# converter.net
KiCad netlist of a schematic drawn in EAGLE
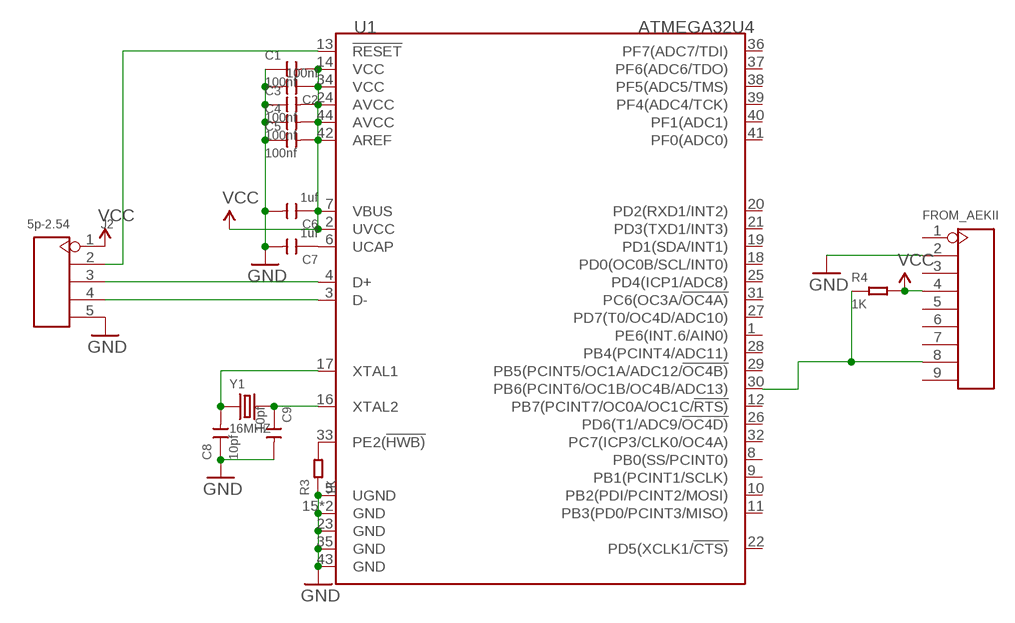
[diagram p0: schematic, sheet 1]
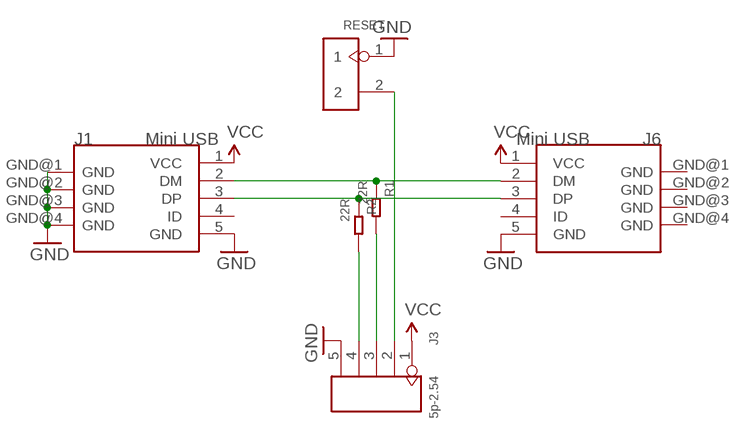
[diagram p1: schematic, sheet 2]

(export (version "E")
  (design (tool "Eeschema 10.0.6"))
  (components
    (comp (ref "J1")
      (value "Mini USB")
      (footprint "eagle-import:MINIUSB5+4P-0.8-90D")
      (fields (field (name "MPN") "ST-USB-013A"))
      (libsource (lib "eagle-import") (part "MINI-USB2.0-RECEPT-5POS-4-LEGS-(ST-USB-013A)"))
    )
    (comp (ref "J3")
      (value "5p-2.54")
      (footprint "eagle-import:H5-2.54")
      (fields (field (name "MPN") "F185-1105A0BSYA1"))
      (libsource (lib "eagle-import") (part "DIP-BLACK-FEMALE-HEADER-VERT(5P-2.54)"))
    )
    (comp (ref "J6")
      (value "Mini USB")
      (footprint "eagle-import:MINIUSB5+4P-0.8-90D")
      (fields (field (name "MPN") "ST-USB-013A"))
      (libsource (lib "eagle-import") (part "MINI-USB2.0-RECEPT-5POS-4-LEGS-(ST-USB-013A)"))
    )
    (comp (ref "R1")
      (value "22R")
      (footprint "eagle-import:R0603")
      (fields (field (name "MPN") "RC0603JR-0722RL"))
      (libsource (lib "eagle-import") (part "SMD-RES-22R-5%-1/10W(0603)"))
    )
    (comp (ref "R2")
      (value "22R")
      (footprint "eagle-import:R0603")
      (fields (field (name "MPN") "RC0603JR-0722RL"))
      (libsource (lib "eagle-import") (part "SMD-RES-22R-5%-1/10W(0603)"))
    )
    (comp (ref "RESET")
      (value "DIP-BLACK-FEMALE-HEADER-VERT(2P-2.54)")
      (footprint "eagle-import:H2-2.54")
      (fields (field (name "MPN") "F185-1102A1BSYA1"))
      (libsource (lib "eagle-import") (part "DIP-BLACK-FEMALE-HEADER-VERT(2P-2.54)"))
    )
    (comp (ref "C1")
      (value "100nf")
      (footprint "eagle-import:C0603")
      (fields (field (name "MPN") "CC0603KRX7R9BB104"))
      (libsource (lib "eagle-import") (part "CERAMIC-100NF-50V-10%-X7R(0603)"))
    )
    (comp (ref "C2")
      (value "100nf")
      (footprint "eagle-import:C0603")
      (fields (field (name "MPN") "CC0603KRX7R9BB104"))
      (libsource (lib "eagle-import") (part "CERAMIC-100NF-50V-10%-X7R(0603)"))
    )
    (comp (ref "C3")
      (value "100nf")
      (footprint "eagle-import:C0603")
      (fields (field (name "MPN") "CC0603KRX7R9BB104"))
      (libsource (lib "eagle-import") (part "CERAMIC-100NF-50V-10%-X7R(0603)"))
    )
    (comp (ref "C4")
      (value "100nf")
      (footprint "eagle-import:C0603")
      (fields (field (name "MPN") "CC0603KRX7R9BB104"))
      (libsource (lib "eagle-import") (part "CERAMIC-100NF-50V-10%-X7R(0603)"))
    )
    (comp (ref "C5")
      (value "100nf")
      (footprint "eagle-import:C0603")
      (fields (field (name "MPN") "CC0603KRX7R9BB104"))
      (libsource (lib "eagle-import") (part "CERAMIC-100NF-50V-10%-X7R(0603)"))
    )
    (comp (ref "C6")
      (value "1uf")
      (footprint "eagle-import:C0603")
      (fields (field (name "MPN") "CC0603KRX7R8BB105"))
      (libsource (lib "eagle-import") (part "CERAMIC-1UF-25V-10%-X7R(0603)"))
    )
    (comp (ref "C7")
      (value "1uf")
      (footprint "eagle-import:C0603")
      (fields (field (name "MPN") "CC0603KRX7R8BB105"))
      (libsource (lib "eagle-import") (part "CERAMIC-1UF-25V-10%-X7R(0603)"))
    )
    (comp (ref "C8")
      (value "10pf")
      (footprint "eagle-import:C0603")
      (libsource (lib "eagle-import") (part "CERAMIC-10PF-50V-5%-NPO(0603)"))
    )
    (comp (ref "C9")
      (value "10pf")
      (footprint "eagle-import:C0603")
      (libsource (lib "eagle-import") (part "CERAMIC-10PF-50V-5%-NPO(0603)"))
    )
    (comp (ref "FROM_AEKII")
      (value "DIP-BLACK-FEMALE-HEADER-VERT(9P-2.0)")
      (footprint "eagle-import:H9-2.0")
      (libsource (lib "eagle-import") (part "DIP-BLACK-FEMALE-HEADER-VERT(9P-2.0)"))
    )
    (comp (ref "J2")
      (value "5p-2.54")
      (footprint "eagle-import:H5-2.54")
      (fields (field (name "MPN") "F185-1105A0BSYA1"))
      (libsource (lib "eagle-import") (part "DIP-BLACK-FEMALE-HEADER-VERT(5P-2.54)"))
    )
    (comp (ref "R3")
      (value "1K")
      (footprint "eagle-import:R0603")
      (fields (field (name "MPN") "RC0603FR-071KL"))
      (libsource (lib "eagle-import") (part "SMD-RES-1K-1%-1/10W(0603)"))
    )
    (comp (ref "R4")
      (value "1K")
      (footprint "eagle-import:R0603")
      (fields (field (name "MPN") "RC0603FR-071KL"))
      (libsource (lib "eagle-import") (part "SMD-RES-1K-1%-1/10W(0603)"))
    )
    (comp (ref "U1")
      (value "ATMEGA32U4")
      (footprint "eagle-import:QFN44G-0.5-7X7MM")
      (fields (field (name "MPN") "ATMEGA32U4-MUR"))
      (libsource (lib "eagle-import") (part "MCU-ATMEGA32U4-MUR(VQFN44)"))
    )
    (comp (ref "Y1")
      (value "16MHZ")
      (footprint "eagle-import:X2-SMD-5.0X3.2X1.3MM")
      (fields (field (name "MPN") "X053201602002"))
      (libsource (lib "eagle-import") (part "SMD-CRYSTAL-16MHZ-8PF-20PPM-40R(2P-5.0X3.2MM)"))
    )
  )
  (nets
    (net (code "1") (name "GND") (class "Default")
      (node (ref "C1") (pin "1") (pinfunction "1_1") (pintype "passive"))
      (node (ref "C2") (pin "2") (pinfunction "2_2") (pintype "passive"))
      (node (ref "C3") (pin "1") (pinfunction "1_1") (pintype "passive"))
      (node (ref "C4") (pin "1") (pinfunction "1_1") (pintype "passive"))
      (node (ref "C5") (pin "1") (pinfunction "1_1") (pintype "passive"))
      (node (ref "C6") (pin "2") (pinfunction "2_2") (pintype "passive"))
      (node (ref "C7") (pin "2") (pinfunction "2_2") (pintype "passive"))
      (node (ref "C8") (pin "1") (pinfunction "1_1") (pintype "passive"))
      (node (ref "C9") (pin "2") (pinfunction "2_2") (pintype "passive"))
      (node (ref "FROM_AEKII") (pin "2") (pinfunction "2_2") (pintype "bidirectional"))
      (node (ref "J1") (pin "5") (pinfunction "GND_5") (pintype "bidirectional"))
      (node (ref "J1") (pin "GND@1") (pinfunction "GND_GND@1") (pintype "bidirectional"))
      (node (ref "J1") (pin "GND@2") (pinfunction "GND_GND@2") (pintype "bidirectional"))
      (node (ref "J1") (pin "GND@3") (pinfunction "GND_GND@3") (pintype "bidirectional"))
      (node (ref "J1") (pin "GND@4") (pinfunction "GND_GND@4") (pintype "bidirectional"))
      (node (ref "J2") (pin "5") (pinfunction "5_5") (pintype "bidirectional"))
      (node (ref "J3") (pin "5") (pinfunction "5_5") (pintype "bidirectional"))
      (node (ref "J6") (pin "5") (pinfunction "GND_5") (pintype "bidirectional"))
      (node (ref "R3") (pin "1") (pinfunction "1_1") (pintype "passive"))
      (node (ref "RESET") (pin "1") (pinfunction "1_1") (pintype "bidirectional"))
      (node (ref "U1") (pin "15") (pinfunction "GND_15") (pintype "bidirectional"))
      (node (ref "U1") (pin "23") (pinfunction "GND_23") (pintype "bidirectional"))
      (node (ref "U1") (pin "35") (pinfunction "GND_35") (pintype "bidirectional"))
      (node (ref "U1") (pin "43") (pinfunction "GND_43") (pintype "bidirectional"))
      (node (ref "U1") (pin "5") (pinfunction "UGND_5") (pintype "bidirectional"))
      (node (ref "U1") (pin "TAB") (pinfunction "GND_TAB") (pintype "bidirectional"))
    )
    (net (code "2") (name "Net-(J1-DM)") (class "Default")
      (node (ref "J1") (pin "2") (pinfunction "DM_2") (pintype "bidirectional"))
      (node (ref "J6") (pin "2") (pinfunction "DM_2") (pintype "bidirectional"))
      (node (ref "R1") (pin "1") (pinfunction "1_1") (pintype "passive"))
    )
    (net (code "3") (name "Net-(J1-DP)") (class "Default")
      (node (ref "J1") (pin "3") (pinfunction "DP_3") (pintype "bidirectional"))
      (node (ref "J6") (pin "3") (pinfunction "DP_3") (pintype "bidirectional"))
      (node (ref "R2") (pin "1") (pinfunction "1_1") (pintype "passive"))
    )
    (net (code "4") (name "Net-(J3-Pad2)") (class "Default")
      (node (ref "J3") (pin "2") (pinfunction "2_2") (pintype "bidirectional"))
      (node (ref "RESET") (pin "2") (pinfunction "2_2") (pintype "bidirectional"))
    )
    (net (code "5") (name "Net-(J3-Pad3)") (class "Default")
      (node (ref "J3") (pin "3") (pinfunction "3_3") (pintype "bidirectional"))
      (node (ref "R1") (pin "2") (pinfunction "2_2") (pintype "passive"))
    )
    (net (code "6") (name "Net-(J3-Pad4)") (class "Default")
      (node (ref "J3") (pin "4") (pinfunction "4_4") (pintype "bidirectional"))
      (node (ref "R2") (pin "2") (pinfunction "2_2") (pintype "passive"))
    )
    (net (code "7") (name "Net-(U1-D+)") (class "Default")
      (node (ref "J2") (pin "3") (pinfunction "3_3") (pintype "bidirectional"))
      (node (ref "U1") (pin "4") (pinfunction "D+_4") (pintype "bidirectional"))
    )
    (net (code "8") (name "Net-(U1-D-)") (class "Default")
      (node (ref "J2") (pin "4") (pinfunction "4_4") (pintype "bidirectional"))
      (node (ref "U1") (pin "3") (pinfunction "D-_3") (pintype "bidirectional"))
    )
    (net (code "9") (name "Net-(U1-PB6(PCINT6{slash}OC1B{slash}OC4B{slash}ADC13))") (class "Default")
      (node (ref "FROM_AEKII") (pin "8") (pinfunction "8_8") (pintype "bidirectional"))
      (node (ref "R4") (pin "1") (pinfunction "1_1") (pintype "passive"))
      (node (ref "U1") (pin "30") (pinfunction "PB6(PCINT6/OC1B/OC4B/ADC13)_30") (pintype "bidirectional"))
    )
    (net (code "10") (name "Net-(U1-PE2(~{HWB}))") (class "Default")
      (node (ref "R3") (pin "2") (pinfunction "2_2") (pintype "passive"))
      (node (ref "U1") (pin "33") (pinfunction "PE2(~{HWB})_33") (pintype "bidirectional"))
    )
    (net (code "11") (name "Net-(U1-UCAP)") (class "Default")
      (node (ref "C7") (pin "1") (pinfunction "1_1") (pintype "passive"))
      (node (ref "U1") (pin "6") (pinfunction "UCAP_6") (pintype "bidirectional"))
    )
    (net (code "12") (name "Net-(U1-XTAL1)") (class "Default")
      (node (ref "C8") (pin "2") (pinfunction "2_2") (pintype "passive"))
      (node (ref "U1") (pin "17") (pinfunction "XTAL1_17") (pintype "bidirectional"))
      (node (ref "Y1") (pin "1") (pinfunction "1_1") (pintype "passive"))
    )
    (net (code "13") (name "Net-(U1-XTAL2)") (class "Default")
      (node (ref "C9") (pin "1") (pinfunction "1_1") (pintype "passive"))
      (node (ref "U1") (pin "16") (pinfunction "XTAL2_16") (pintype "bidirectional"))
      (node (ref "Y1") (pin "2") (pinfunction "2_2") (pintype "passive"))
    )
    (net (code "14") (name "Net-(U1-~{RESET})") (class "Default")
      (node (ref "J2") (pin "2") (pinfunction "2_2") (pintype "bidirectional"))
      (node (ref "U1") (pin "13") (pinfunction "~{RESET}_13") (pintype "bidirectional"))
    )
    (net (code "15") (name "VCC") (class "Default")
      (node (ref "C1") (pin "2") (pinfunction "2_2") (pintype "passive"))
      (node (ref "C2") (pin "1") (pinfunction "1_1") (pintype "passive"))
      (node (ref "C3") (pin "2") (pinfunction "2_2") (pintype "passive"))
      (node (ref "C4") (pin "2") (pinfunction "2_2") (pintype "passive"))
      (node (ref "C5") (pin "2") (pinfunction "2_2") (pintype "passive"))
      (node (ref "C6") (pin "1") (pinfunction "1_1") (pintype "passive"))
      (node (ref "FROM_AEKII") (pin "4") (pinfunction "4_4") (pintype "bidirectional"))
      (node (ref "J1") (pin "1") (pinfunction "VCC_1") (pintype "bidirectional"))
      (node (ref "J2") (pin "1") (pinfunction "1_1") (pintype "bidirectional"))
      (node (ref "J3") (pin "1") (pinfunction "1_1") (pintype "bidirectional"))
      (node (ref "J6") (pin "1") (pinfunction "VCC_1") (pintype "bidirectional"))
      (node (ref "R4") (pin "2") (pinfunction "2_2") (pintype "passive"))
      (node (ref "U1") (pin "14") (pinfunction "VCC_14") (pintype "bidirectional"))
      (node (ref "U1") (pin "2") (pinfunction "UVCC_2") (pintype "bidirectional"))
      (node (ref "U1") (pin "24") (pinfunction "AVCC_24") (pintype "bidirectional"))
      (node (ref "U1") (pin "34") (pinfunction "VCC_34") (pintype "bidirectional"))
      (node (ref "U1") (pin "42") (pinfunction "AREF_42") (pintype "bidirectional"))
      (node (ref "U1") (pin "44") (pinfunction "AVCC_44") (pintype "bidirectional"))
      (node (ref "U1") (pin "7") (pinfunction "VBUS_7") (pintype "bidirectional"))
    )
    (net (code "16") (name "unconnected-(FROM_AEKII-Pad1)") (class "Default")
      (node (ref "FROM_AEKII") (pin "1") (pinfunction "1_1") (pintype "bidirectional"))
    )
    (net (code "17") (name "unconnected-(FROM_AEKII-Pad3)") (class "Default")
      (node (ref "FROM_AEKII") (pin "3") (pinfunction "3_3") (pintype "bidirectional"))
    )
    (net (code "18") (name "unconnected-(FROM_AEKII-Pad5)") (class "Default")
      (node (ref "FROM_AEKII") (pin "5") (pinfunction "5_5") (pintype "bidirectional"))
    )
    (net (code "19") (name "unconnected-(FROM_AEKII-Pad6)") (class "Default")
      (node (ref "FROM_AEKII") (pin "6") (pinfunction "6_6") (pintype "bidirectional"))
    )
    (net (code "20") (name "unconnected-(FROM_AEKII-Pad7)") (class "Default")
      (node (ref "FROM_AEKII") (pin "7") (pinfunction "7_7") (pintype "bidirectional"))
    )
    (net (code "21") (name "unconnected-(FROM_AEKII-Pad9)") (class "Default")
      (node (ref "FROM_AEKII") (pin "9") (pinfunction "9_9") (pintype "bidirectional"))
    )
    (net (code "22") (name "unconnected-(J1-ID-Pad4)") (class "Default")
      (node (ref "J1") (pin "4") (pinfunction "ID_4") (pintype "bidirectional"))
    )
    (net (code "23") (name "unconnected-(J6-GND-PadGND@1)") (class "Default")
      (node (ref "J6") (pin "GND@1") (pinfunction "GND_GND@1") (pintype "bidirectional"))
    )
    (net (code "24") (name "unconnected-(J6-GND-PadGND@2)") (class "Default")
      (node (ref "J6") (pin "GND@2") (pinfunction "GND_GND@2") (pintype "bidirectional"))
    )
    (net (code "25") (name "unconnected-(J6-GND-PadGND@3)") (class "Default")
      (node (ref "J6") (pin "GND@3") (pinfunction "GND_GND@3") (pintype "bidirectional"))
    )
    (net (code "26") (name "unconnected-(J6-GND-PadGND@4)") (class "Default")
      (node (ref "J6") (pin "GND@4") (pinfunction "GND_GND@4") (pintype "bidirectional"))
    )
    (net (code "27") (name "unconnected-(J6-ID-Pad4)") (class "Default")
      (node (ref "J6") (pin "4") (pinfunction "ID_4") (pintype "bidirectional"))
    )
    (net (code "28") (name "unconnected-(U1-PB0(SS{slash}PCINT0)-Pad8)") (class "Default")
      (node (ref "U1") (pin "8") (pinfunction "PB0(SS/PCINT0)_8") (pintype "bidirectional"))
    )
    (net (code "29") (name "unconnected-(U1-PB1(PCINT1{slash}SCLK)-Pad9)") (class "Default")
      (node (ref "U1") (pin "9") (pinfunction "PB1(PCINT1/SCLK)_9") (pintype "bidirectional"))
    )
    (net (code "30") (name "unconnected-(U1-PB2(PDI{slash}PCINT2{slash}MOSI)-Pad10)") (class "Default")
      (node (ref "U1") (pin "10") (pinfunction "PB2(PDI/PCINT2/MOSI)_10") (pintype "bidirectional"))
    )
    (net (code "31") (name "unconnected-(U1-PB3(PD0{slash}PCINT3{slash}MISO)-Pad11)") (class "Default")
      (node (ref "U1") (pin "11") (pinfunction "PB3(PD0/PCINT3/MISO)_11") (pintype "bidirectional"))
    )
    (net (code "32") (name "unconnected-(U1-PB4(PCINT4{slash}ADC11)-Pad28)") (class "Default")
      (node (ref "U1") (pin "28") (pinfunction "PB4(PCINT4/ADC11)_28") (pintype "bidirectional"))
    )
    (net (code "33") (name "unconnected-(U1-PB5(PCINT5{slash}OC1A{slash}ADC12{slash}~{OC4B})-Pad29)") (class "Default")
      (node (ref "U1") (pin "29") (pinfunction "PB5(PCINT5/OC1A/ADC12/~{OC4B})_29") (pintype "bidirectional"))
    )
    (net (code "34") (name "unconnected-(U1-PB7(PCINT7{slash}OC0A{slash}OC1C{slash}~{RTS})-Pad12)") (class "Default")
      (node (ref "U1") (pin "12") (pinfunction "PB7(PCINT7/OC0A/OC1C/~{RTS})_12") (pintype "bidirectional"))
    )
    (net (code "35") (name "unconnected-(U1-PC6(OC3A{slash}~{OC4A})-Pad31)") (class "Default")
      (node (ref "U1") (pin "31") (pinfunction "PC6(OC3A/~{OC4A})_31") (pintype "bidirectional"))
    )
    (net (code "36") (name "unconnected-(U1-PC7(ICP3{slash}CLK0{slash}OC4A)-Pad32)") (class "Default")
      (node (ref "U1") (pin "32") (pinfunction "PC7(ICP3/CLK0/OC4A)_32") (pintype "bidirectional"))
    )
    (net (code "37") (name "unconnected-(U1-PD0(OC0B{slash}SCL{slash}INT0)-Pad18)") (class "Default")
      (node (ref "U1") (pin "18") (pinfunction "PD0(OC0B/SCL/INT0)_18") (pintype "bidirectional"))
    )
    (net (code "38") (name "unconnected-(U1-PD1(SDA{slash}INT1)-Pad19)") (class "Default")
      (node (ref "U1") (pin "19") (pinfunction "PD1(SDA/INT1)_19") (pintype "bidirectional"))
    )
    (net (code "39") (name "unconnected-(U1-PD2(RXD1{slash}INT2)-Pad20)") (class "Default")
      (node (ref "U1") (pin "20") (pinfunction "PD2(RXD1/INT2)_20") (pintype "bidirectional"))
    )
    (net (code "40") (name "unconnected-(U1-PD3(TXD1{slash}INT3)-Pad21)") (class "Default")
      (node (ref "U1") (pin "21") (pinfunction "PD3(TXD1/INT3)_21") (pintype "bidirectional"))
    )
    (net (code "41") (name "unconnected-(U1-PD4(ICP1{slash}ADC8)-Pad25)") (class "Default")
      (node (ref "U1") (pin "25") (pinfunction "PD4(ICP1/ADC8)_25") (pintype "bidirectional"))
    )
    (net (code "42") (name "unconnected-(U1-PD5(XCLK1{slash}~{CTS})-Pad22)") (class "Default")
      (node (ref "U1") (pin "22") (pinfunction "PD5(XCLK1/~{CTS})_22") (pintype "bidirectional"))
    )
    (net (code "43") (name "unconnected-(U1-PD6(T1{slash}ADC9{slash}~{OC4D})-Pad26)") (class "Default")
      (node (ref "U1") (pin "26") (pinfunction "PD6(T1/ADC9/~{OC4D})_26") (pintype "bidirectional"))
    )
    (net (code "44") (name "unconnected-(U1-PD7(T0{slash}OC4D{slash}ADC10)-Pad27)") (class "Default")
      (node (ref "U1") (pin "27") (pinfunction "PD7(T0/OC4D/ADC10)_27") (pintype "bidirectional"))
    )
    (net (code "45") (name "unconnected-(U1-PE6(INT.6{slash}AIN0)-Pad1)") (class "Default")
      (node (ref "U1") (pin "1") (pinfunction "PE6(INT.6/AIN0)_1") (pintype "bidirectional"))
    )
    (net (code "46") (name "unconnected-(U1-PF0(ADC0)-Pad41)") (class "Default")
      (node (ref "U1") (pin "41") (pinfunction "PF0(ADC0)_41") (pintype "bidirectional"))
    )
    (net (code "47") (name "unconnected-(U1-PF1(ADC1)-Pad40)") (class "Default")
      (node (ref "U1") (pin "40") (pinfunction "PF1(ADC1)_40") (pintype "bidirectional"))
    )
    (net (code "48") (name "unconnected-(U1-PF4(ADC4{slash}TCK)-Pad39)") (class "Default")
      (node (ref "U1") (pin "39") (pinfunction "PF4(ADC4/TCK)_39") (pintype "bidirectional"))
    )
    (net (code "49") (name "unconnected-(U1-PF5(ADC5{slash}TMS)-Pad38)") (class "Default")
      (node (ref "U1") (pin "38") (pinfunction "PF5(ADC5/TMS)_38") (pintype "bidirectional"))
    )
    (net (code "50") (name "unconnected-(U1-PF6(ADC6{slash}TDO)-Pad37)") (class "Default")
      (node (ref "U1") (pin "37") (pinfunction "PF6(ADC6/TDO)_37") (pintype "bidirectional"))
    )
    (net (code "51") (name "unconnected-(U1-PF7(ADC7{slash}TDI)-Pad36)") (class "Default")
      (node (ref "U1") (pin "36") (pinfunction "PF7(ADC7/TDI)_36") (pintype "bidirectional"))
    )
  )
)
